# Dot.net
KiCad netlist of a schematic drawn in EAGLE
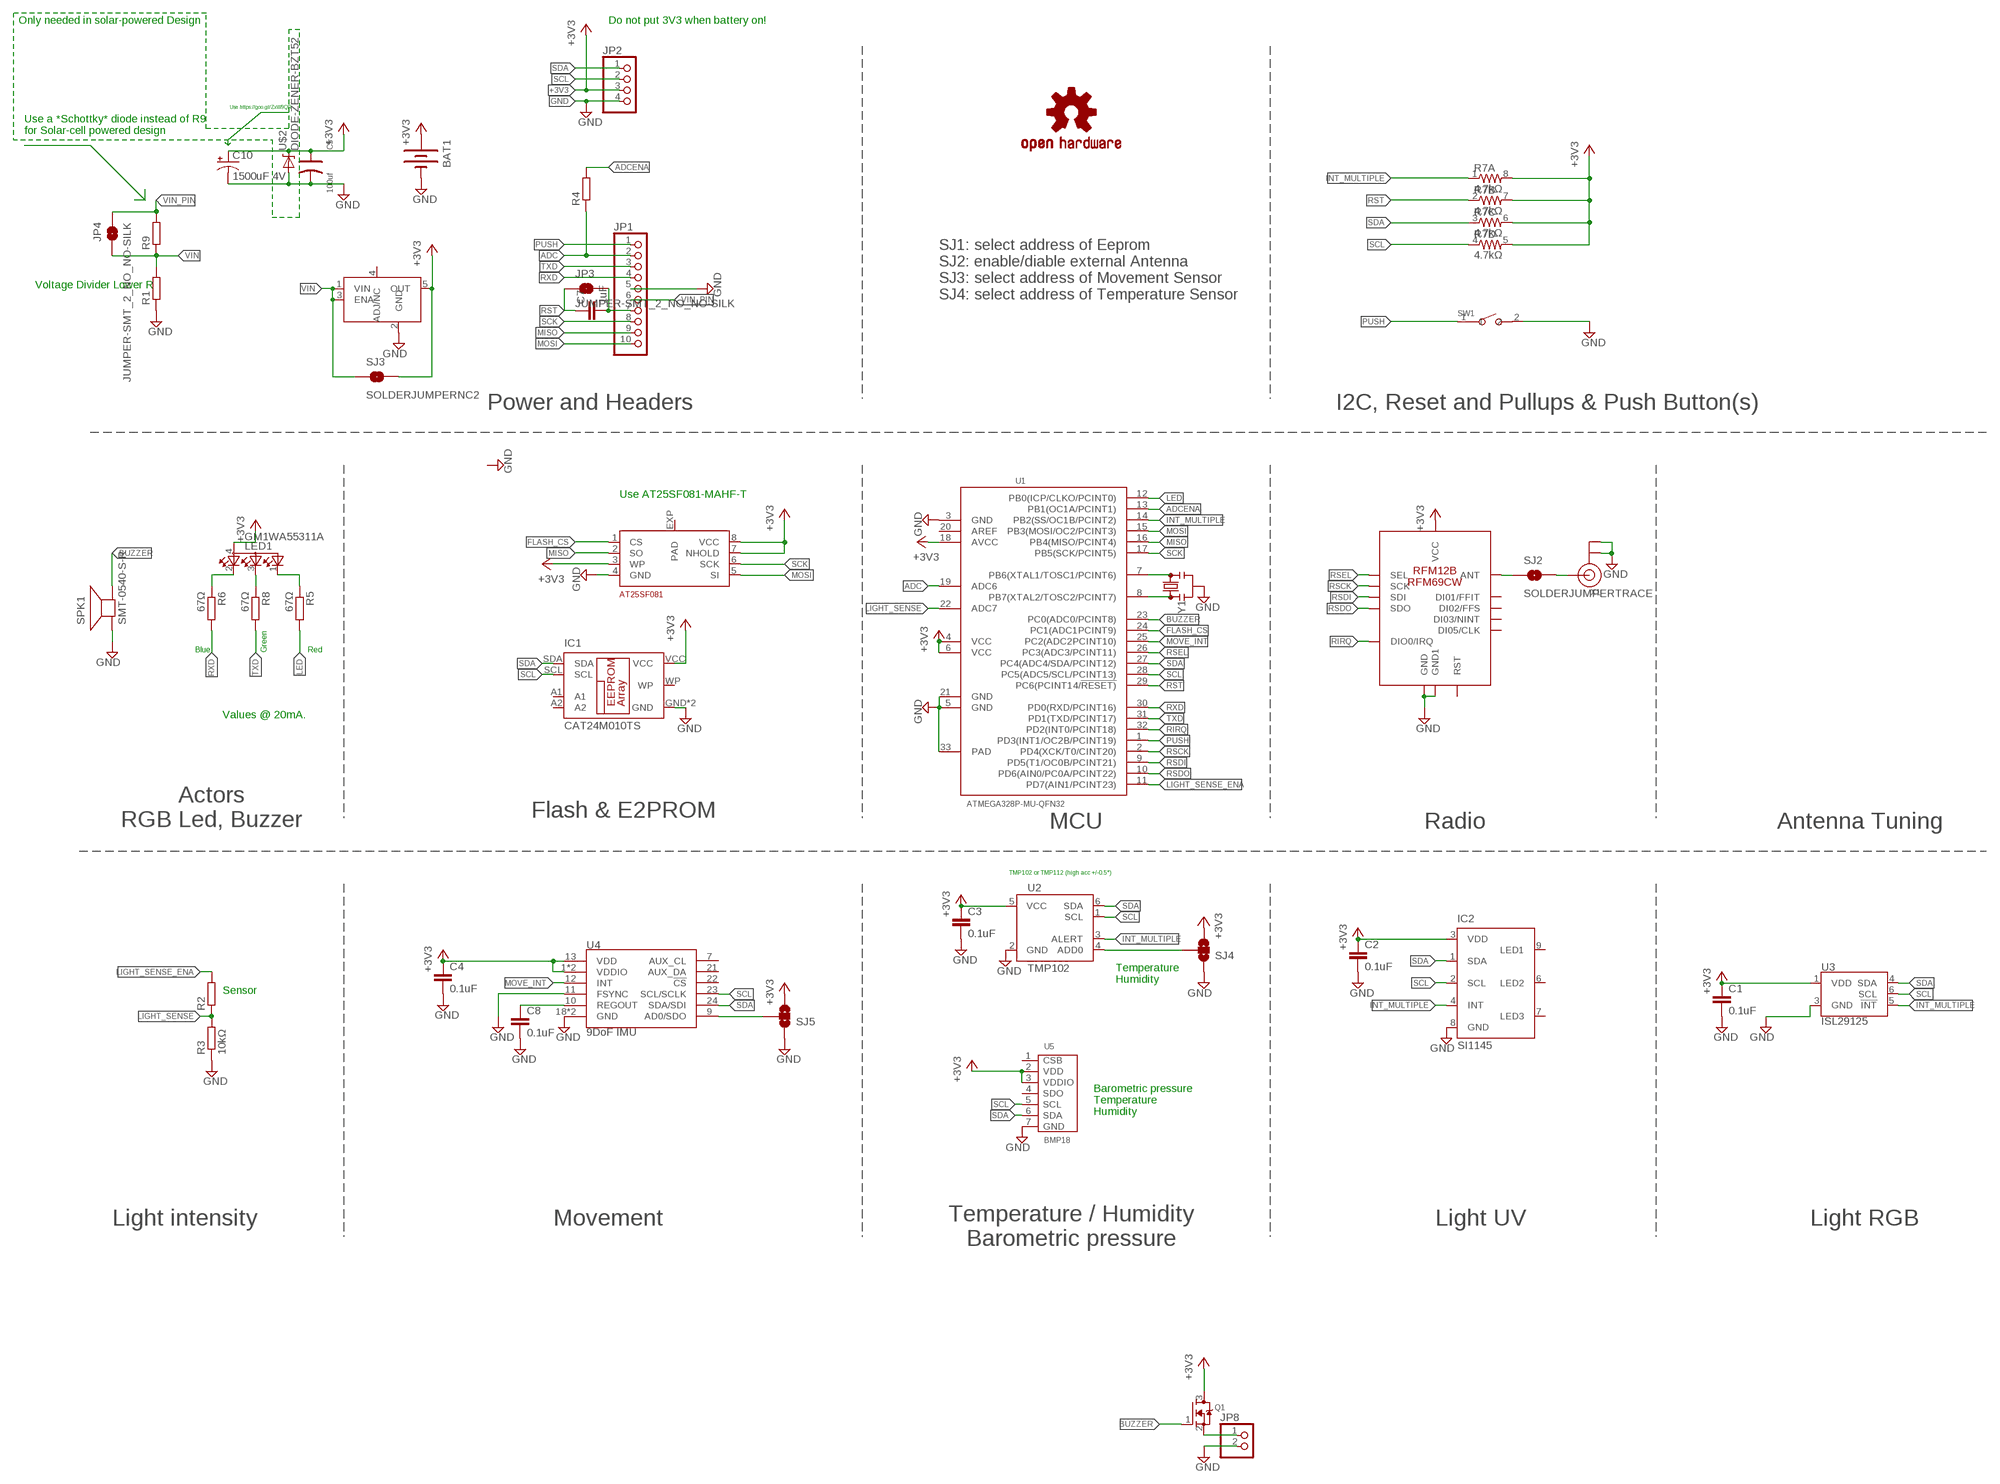
[diagram p0: schematic, sheet 1]
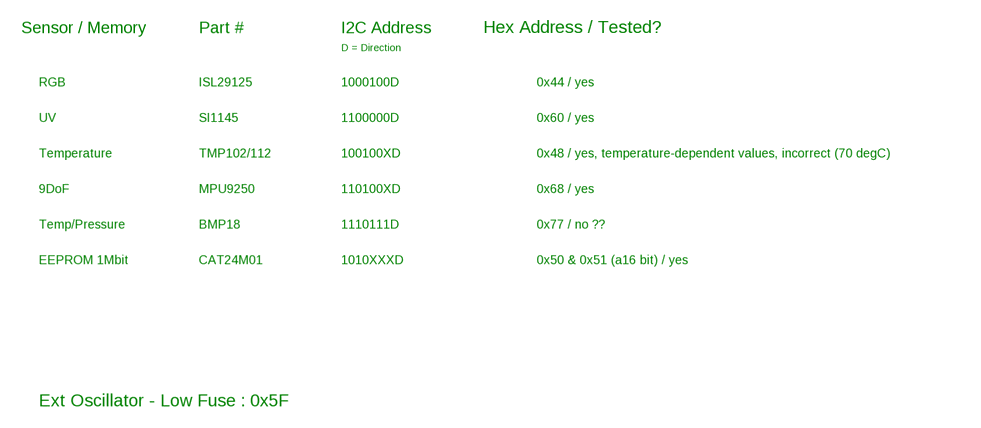
[diagram p1: schematic, sheet 2]

(export (version "E")
  (design (tool "Eeschema 10.0.6"))
  (components
    (comp (ref "BAT1")
      (value "BATTERY20PTH")
      (footprint "eagle-import:BATTCOM_20MM_PTH")
      (libsource (lib "eagle-import") (part "BATTERY20PTH"))
    )
    (comp (ref "C1")
      (value "0.1uF")
      (footprint "eagle-import:C0603")
      (libsource (lib "eagle-import") (part "C-EUC0603"))
    )
    (comp (ref "C2")
      (value "0.1uF")
      (footprint "eagle-import:C0603")
      (libsource (lib "eagle-import") (part "C-EUC0603"))
    )
    (comp (ref "C3")
      (value "0.1uF")
      (footprint "eagle-import:C0603")
      (libsource (lib "eagle-import") (part "C-EUC0603"))
    )
    (comp (ref "C4")
      (value "0.1uF")
      (footprint "eagle-import:C0603")
      (libsource (lib "eagle-import") (part "C-EUC0603"))
    )
    (comp (ref "C5")
      (value "100uf")
      (footprint "eagle-import:AVX-A")
      (fields (field (name "MPN") "TLJA107M006R0800"))
      (libsource (lib "eagle-import") (part "TANTALUM-SMD-100UF-6.3V(AVX-A)"))
    )
    (comp (ref "C7")
      (value "1uF")
      (footprint "eagle-import:C0603")
      (libsource (lib "eagle-import") (part "C-EUC0603"))
    )
    (comp (ref "C8")
      (value "0.1uF")
      (footprint "eagle-import:C0603")
      (libsource (lib "eagle-import") (part "C-EUC0603"))
    )
    (comp (ref "C10")
      (value "1500uF 4V")
      (footprint "eagle-import:CT7343")
      (libsource (lib "eagle-import") (part "CPOL-USCT7343"))
    )
    (comp (ref "IC1")
      (value "CAT24M010TS")
      (footprint "eagle-import:TSSOP8")
      (fields (field (name "MF") "On Semiconductor") (field (name "MPN") "24C00T-E/ST"))
      (libsource (lib "eagle-import") (part "CAT24M01TS0"))
    )
    (comp (ref "IC2")
      (value "SI1145")
      (footprint "eagle-import:QFN-10")
      (libsource (lib "eagle-import") (part "SI1145"))
    )
    (comp (ref "JP1")
      (value "PINHD-1X10")
      (footprint "eagle-import:1X10")
      (libsource (lib "eagle-import") (part "PINHD-1X10"))
    )
    (comp (ref "JP2")
      (value "PINHD-1X4")
      (footprint "eagle-import:1X04")
      (libsource (lib "eagle-import") (part "PINHD-1X4"))
    )
    (comp (ref "JP3")
      (value "JUMPER-SMT_2_NO_NO-SILK")
      (footprint "eagle-import:SMT-JUMPER_2_NO_NO-SILK")
      (libsource (lib "eagle-import") (part "JUMPER-SMT_2_NO_NO-SILK"))
    )
    (comp (ref "JP4")
      (value "JUMPER-SMT_2_NO_NO-SILK")
      (footprint "eagle-import:SMT-JUMPER_2_NO_NO-SILK")
      (libsource (lib "eagle-import") (part "JUMPER-SMT_2_NO_NO-SILK"))
    )
    (comp (ref "JP8")
      (value "PINHD-1X2")
      (footprint "eagle-import:1X02")
      (libsource (lib "eagle-import") (part "PINHD-1X2"))
    )
    (comp (ref "LED1")
      (value "GM1WA55311A")
      (footprint "eagle-import:GM1WA55311A")
      (libsource (lib "eagle-import") (part "GM1WA55311A"))
    )
    (comp (ref "LOGO1")
      (value "OSHW-LOGOS")
      (footprint "eagle-import:OSHW-LOGO-S")
      (libsource (lib "eagle-import") (part "OSHW-LOGOS"))
    )
    (comp (ref "Q1")
      (value "MOSFET-NREFLOW")
      (footprint "eagle-import:SOT23")
      (libsource (lib "eagle-import") (part "MOSFET-NREFLOW"))
    )
    (comp (ref "R1")
      (value "R-EU_R0603")
      (footprint "eagle-import:R0603")
      (libsource (lib "eagle-import") (part "R-EU_R0603"))
    )
    (comp (ref "R2")
      (value "R-EU_R0805")
      (footprint "eagle-import:R0805")
      (libsource (lib "eagle-import") (part "R-EU_R0805"))
    )
    (comp (ref "R3")
      (value "10kΩ")
      (footprint "eagle-import:R0603")
      (libsource (lib "eagle-import") (part "R-EU_R0603"))
    )
    (comp (ref "R4")
      (value "R-EU_R0603")
      (footprint "eagle-import:R0603")
      (libsource (lib "eagle-import") (part "R-EU_R0603"))
    )
    (comp (ref "R5")
      (value "67Ω")
      (footprint "eagle-import:R0603")
      (libsource (lib "eagle-import") (part "R-EU_R0603"))
    )
    (comp (ref "R6")
      (value "67Ω")
      (footprint "eagle-import:R0603")
      (libsource (lib "eagle-import") (part "R-EU_R0603"))
    )
    (comp (ref "R7")
      (value "4.7kΩ")
      (footprint "eagle-import:0603-ARV")
      (libsource (lib "eagle-import") (part "RESISTOR-ARRAY0603-ARV"))
    )
    (comp (ref "R8")
      (value "67Ω")
      (footprint "eagle-import:R0603")
      (libsource (lib "eagle-import") (part "R-EU_R0603"))
    )
    (comp (ref "R9")
      (value "R-EU_R0603")
      (footprint "eagle-import:R0603")
      (libsource (lib "eagle-import") (part "R-EU_R0603"))
    )
    (comp (ref "SJ2")
      (value "SOLDERJUMPERTRACE")
      (footprint "eagle-import:SJ_2S-TRACE")
      (libsource (lib "eagle-import") (part "SOLDERJUMPERTRACE"))
    )
    (comp (ref "SJ3")
      (value "SOLDERJUMPERNC2")
      (footprint "eagle-import:SJ_2S-NOTRACE")
      (libsource (lib "eagle-import") (part "SOLDERJUMPERNC2"))
    )
    (comp (ref "SJ4")
      (value "SOLDERJUMPER_2WAYS")
      (footprint "eagle-import:SJ_3")
      (libsource (lib "eagle-import") (part "SOLDERJUMPER_2WAYS"))
    )
    (comp (ref "SJ5")
      (value "SOLDERJUMPER_2WAYS")
      (footprint "eagle-import:SJ_3")
      (libsource (lib "eagle-import") (part "SOLDERJUMPER_2WAYS"))
    )
    (comp (ref "SPK1")
      (value "SMT-0540-S-R")
      (footprint "eagle-import:SMT-0540-S-R")
      (libsource (lib "eagle-import") (part "SMT-0540-S-R"))
    )
    (comp (ref "SW1")
      (value "SMD-BUTTON(2P-6.0X3.0X2.5MM)-DHT-1163S")
      (footprint "eagle-import:SW2-4.0-6.0X3.0X2.5MM")
      (libsource (lib "eagle-import") (part "SMD-BUTTON(2P-6.0X3.0X2.5MM)-DHT-1163S"))
    )
    (comp (ref "U$1")
      (value "RFM12B/69CW")
      (footprint "eagle-import:RFM12B_69CW")
      (libsource (lib "eagle-import") (part "RFM12B/69CW"))
    )
    (comp (ref "U$2")
      (value "DIODE-ZENER-BZT52")
      (footprint "eagle-import:SOD-323")
      (libsource (lib "eagle-import") (part "DIODE-ZENER-BZT52"))
    )
    (comp (ref "U$3")
      (value "AT25SF081")
      (footprint "eagle-import:DFN-2X3")
      (libsource (lib "eagle-import") (part "AT25SF081"))
    )
    (comp (ref "U$4")
      (value "LDCL015")
      (footprint "eagle-import:SOT23-5")
      (libsource (lib "eagle-import") (part "LDCL015"))
    )
    (comp (ref "U1")
      (value "ATMEGA328P-MU-QFN32")
      (footprint "eagle-import:QFN32G-0.5-5X5MM")
      (fields (field (name "MPN") "ATMEGA328P-MU"))
      (libsource (lib "eagle-import") (part "MCU-ATMEGA328P-MU(QFN32)"))
    )
    (comp (ref "U2")
      (value "TMP102")
      (footprint "eagle-import:SOT563")
      (libsource (lib "eagle-import") (part "TMP102"))
    )
    (comp (ref "U3")
      (value "ISL29125")
      (footprint "eagle-import:ODFN-6")
      (libsource (lib "eagle-import") (part "ISL29125"))
    )
    (comp (ref "U4")
      (value "9DoF IMU")
      (footprint "eagle-import:QFN24-3X3")
      (libsource (lib "eagle-import") (part "MPU-9250"))
    )
    (comp (ref "U5")
      (value "BMP18")
      (footprint "eagle-import:LGA7-1.5-3.8X3.6MM")
      (libsource (lib "eagle-import") (part "PRESSURE-BMP180(LGA7)"))
    )
    (comp (ref "X1")
      (value "ANTENNA_U.FL")
      (footprint "eagle-import:U.FL")
      (libsource (lib "eagle-import") (part "ANTENNA_U.FL"))
    )
    (comp (ref "Y1")
      (value "RESONATORSMD-3.2X1.3")
      (footprint "eagle-import:RESONATOR-SMD-3.2X1.3")
      (libsource (lib "eagle-import") (part "RESONATORSMD-3.2X1.3"))
    )
  )
  (nets
    (net (code "1") (name "+3V3") (class "Default")
      (node (ref "BAT1") (pin "1") (pinfunction "+_1") (pintype "power_in"))
      (node (ref "C1") (pin "1") (pinfunction "1_1") (pintype "passive"))
      (node (ref "C10") (pin "+") (pinfunction "+_+") (pintype "passive"))
      (node (ref "C2") (pin "1") (pinfunction "1_1") (pintype "passive"))
      (node (ref "C3") (pin "1") (pinfunction "1_1") (pintype "passive"))
      (node (ref "C4") (pin "1") (pinfunction "1_1") (pintype "passive"))
      (node (ref "C5") (pin "+") (pinfunction "+_+") (pintype "passive"))
      (node (ref "IC1") (pin "VCC") (pinfunction "VCC_VCC") (pintype "power_in"))
      (node (ref "IC2") (pin "3") (pinfunction "VDD_3") (pintype "power_in"))
      (node (ref "JP2") (pin "3") (pinfunction "3_3") (pintype "passive"))
      (node (ref "LED1") (pin "4") (pinfunction "A_4") (pintype "passive"))
      (node (ref "Q1") (pin "3") (pinfunction "D_3") (pintype "bidirectional"))
      (node (ref "R7") (pin "5") (pinfunction "2_5") (pintype "passive"))
      (node (ref "R7") (pin "6") (pinfunction "2_6") (pintype "passive"))
      (node (ref "R7") (pin "7") (pinfunction "2_7") (pintype "passive"))
      (node (ref "R7") (pin "8") (pinfunction "2_8") (pintype "passive"))
      (node (ref "SJ3") (pin "2") (pinfunction "2_2") (pintype "passive"))
      (node (ref "SJ4") (pin "3") (pinfunction "3_3") (pintype "passive"))
      (node (ref "SJ5") (pin "3") (pinfunction "3_3") (pintype "passive"))
      (node (ref "U$1") (pin "VDD") (pinfunction "VCC_VDD") (pintype "power_in"))
      (node (ref "U$2") (pin "1") (pinfunction "C_1") (pintype "passive"))
      (node (ref "U$3") (pin "3") (pinfunction "WP_3") (pintype "bidirectional"))
      (node (ref "U$3") (pin "7") (pinfunction "NHOLD_7") (pintype "bidirectional"))
      (node (ref "U$3") (pin "8") (pinfunction "VCC_8") (pintype "bidirectional"))
      (node (ref "U$4") (pin "5") (pinfunction "OUT_5") (pintype "bidirectional"))
      (node (ref "U1") (pin "18") (pinfunction "AVCC_18") (pintype "bidirectional"))
      (node (ref "U1") (pin "4") (pinfunction "VCC_4") (pintype "bidirectional"))
      (node (ref "U1") (pin "6") (pinfunction "VCC_6") (pintype "bidirectional"))
      (node (ref "U2") (pin "5") (pinfunction "VCC_5") (pintype "bidirectional"))
      (node (ref "U3") (pin "1") (pinfunction "VDD_1") (pintype "bidirectional"))
      (node (ref "U4") (pin "1") (pinfunction "VDDIO_1") (pintype "bidirectional"))
      (node (ref "U4") (pin "13") (pinfunction "VDD_13") (pintype "bidirectional"))
      (node (ref "U4") (pin "8") (pinfunction "VDDIO_8") (pintype "bidirectional"))
      (node (ref "U5") (pin "2") (pinfunction "VDD_2") (pintype "bidirectional"))
      (node (ref "U5") (pin "3") (pinfunction "VDDIO_3") (pintype "bidirectional"))
    )
    (net (code "2") (name "ADC") (class "Default")
      (node (ref "JP1") (pin "2") (pinfunction "2_2") (pintype "passive"))
      (node (ref "R4") (pin "1") (pinfunction "1_1") (pintype "passive"))
      (node (ref "U1") (pin "19") (pinfunction "ADC6_19") (pintype "bidirectional"))
    )
    (net (code "3") (name "ADCENA") (class "Default")
      (node (ref "R4") (pin "2") (pinfunction "2_2") (pintype "passive"))
      (node (ref "U1") (pin "13") (pinfunction "PB1(OC1A/PCINT1)_13") (pintype "bidirectional"))
    )
    (net (code "4") (name "BUZZER") (class "Default")
      (node (ref "Q1") (pin "1") (pinfunction "G_1") (pintype "bidirectional"))
      (node (ref "SPK1") (pin "+") (pinfunction "-_+") (pintype "passive"))
      (node (ref "U1") (pin "23") (pinfunction "PC0(ADC0/PCINT8)_23") (pintype "bidirectional"))
    )
    (net (code "5") (name "FLASH_CS") (class "Default")
      (node (ref "U$3") (pin "1") (pinfunction "CS_1") (pintype "bidirectional"))
      (node (ref "U1") (pin "24") (pinfunction "PC1(ADC1PCINT9)_24") (pintype "bidirectional"))
    )
    (net (code "6") (name "GND") (class "Default")
      (node (ref "BAT1") (pin "2") (pinfunction "-_2") (pintype "power_in"))
      (node (ref "C1") (pin "2") (pinfunction "2_2") (pintype "passive"))
      (node (ref "C10") (pin "-") (pinfunction "-_-") (pintype "passive"))
      (node (ref "C2") (pin "2") (pinfunction "2_2") (pintype "passive"))
      (node (ref "C3") (pin "2") (pinfunction "2_2") (pintype "passive"))
      (node (ref "C4") (pin "2") (pinfunction "2_2") (pintype "passive"))
      (node (ref "C5") (pin "-") (pinfunction "-_-") (pintype "passive"))
      (node (ref "C8") (pin "2") (pinfunction "2_2") (pintype "passive"))
      (node (ref "IC1") (pin "GND") (pinfunction "GND_GND") (pintype "power_in"))
      (node (ref "IC1") (pin "NC") (pinfunction "GND_NC") (pintype "power_in"))
      (node (ref "IC2") (pin "8") (pinfunction "GND_8") (pintype "power_in"))
      (node (ref "JP1") (pin "5") (pinfunction "5_5") (pintype "passive"))
      (node (ref "JP2") (pin "4") (pinfunction "4_4") (pintype "passive"))
      (node (ref "JP8") (pin "2") (pinfunction "2_2") (pintype "passive"))
      (node (ref "R1") (pin "1") (pinfunction "1_1") (pintype "passive"))
      (node (ref "R3") (pin "1") (pinfunction "1_1") (pintype "passive"))
      (node (ref "SJ4") (pin "1") (pinfunction "1_1") (pintype "passive"))
      (node (ref "SJ5") (pin "1") (pinfunction "1_1") (pintype "passive"))
      (node (ref "SPK1") (pin "-") (pinfunction "+_-") (pintype "passive"))
      (node (ref "SW1") (pin "2") (pinfunction "2_2") (pintype "bidirectional"))
      (node (ref "U$1") (pin "GND") (pinfunction "GND_GND") (pintype "power_in"))
      (node (ref "U$1") (pin "GND1") (pinfunction "GND1_GND1") (pintype "power_in"))
      (node (ref "U$2") (pin "2") (pinfunction "A_2") (pintype "passive"))
      (node (ref "U$3") (pin "4") (pinfunction "GND_4") (pintype "bidirectional"))
      (node (ref "U$4") (pin "2") (pinfunction "GND_2") (pintype "bidirectional"))
      (node (ref "U1") (pin "21") (pinfunction "GND_21") (pintype "bidirectional"))
      (node (ref "U1") (pin "3") (pinfunction "GND_3") (pintype "bidirectional"))
      (node (ref "U1") (pin "33") (pinfunction "PAD_33") (pintype "bidirectional"))
      (node (ref "U1") (pin "5") (pinfunction "GND_5") (pintype "bidirectional"))
      (node (ref "U2") (pin "2") (pinfunction "GND_2") (pintype "bidirectional"))
      (node (ref "U3") (pin "3") (pinfunction "GND_3") (pintype "bidirectional"))
      (node (ref "U4") (pin "11") (pinfunction "FSYNC_11") (pintype "bidirectional"))
      (node (ref "U4") (pin "18") (pinfunction "GND_18") (pintype "bidirectional"))
      (node (ref "U4") (pin "20") (pinfunction "GND_20") (pintype "bidirectional"))
      (node (ref "U5") (pin "7") (pinfunction "GND_7") (pintype "bidirectional"))
      (node (ref "X1") (pin "1") (pinfunction "GND_1") (pintype "passive"))
      (node (ref "X1") (pin "2") (pinfunction "GND_2") (pintype "passive"))
      (node (ref "Y1") (pin "2") (pinfunction "2_2") (pintype "passive"))
    )
    (net (code "7") (name "INT_MULTIPLE") (class "Default")
      (node (ref "IC2") (pin "4") (pinfunction "INT_4") (pintype "open_collector"))
      (node (ref "R7") (pin "1") (pinfunction "1_1") (pintype "passive"))
      (node (ref "U1") (pin "14") (pinfunction "PB2(SS/OC1B/PCINT2)_14") (pintype "bidirectional"))
      (node (ref "U2") (pin "3") (pinfunction "ALERT_3") (pintype "bidirectional"))
      (node (ref "U3") (pin "5") (pinfunction "~{INT}_5") (pintype "bidirectional"))
    )
    (net (code "8") (name "LED") (class "Default")
      (node (ref "R5") (pin "2") (pinfunction "2_2") (pintype "passive"))
      (node (ref "U1") (pin "12") (pinfunction "PB0(ICP/CLKO/PCINT0)_12") (pintype "bidirectional"))
    )
    (net (code "9") (name "LIGHT_SENSE") (class "Default")
      (node (ref "R2") (pin "1") (pinfunction "1_1") (pintype "passive"))
      (node (ref "R3") (pin "2") (pinfunction "2_2") (pintype "passive"))
      (node (ref "U1") (pin "22") (pinfunction "ADC7_22") (pintype "bidirectional"))
    )
    (net (code "10") (name "LIGHT_SENSE_ENA") (class "Default")
      (node (ref "R2") (pin "2") (pinfunction "2_2") (pintype "passive"))
      (node (ref "U1") (pin "11") (pinfunction "PD7(AIN1/PCINT23)_11") (pintype "bidirectional"))
    )
    (net (code "11") (name "MISO") (class "Default")
      (node (ref "JP1") (pin "9") (pinfunction "9_9") (pintype "passive"))
      (node (ref "U$3") (pin "2") (pinfunction "SO_2") (pintype "bidirectional"))
      (node (ref "U1") (pin "16") (pinfunction "PB4(MISO/PCINT4)_16") (pintype "bidirectional"))
    )
    (net (code "12") (name "MOSI") (class "Default")
      (node (ref "JP1") (pin "10") (pinfunction "10_10") (pintype "passive"))
      (node (ref "U$3") (pin "5") (pinfunction "SI_5") (pintype "bidirectional"))
      (node (ref "U1") (pin "15") (pinfunction "PB3(MOSI/OC2/PCINT3)_15") (pintype "bidirectional"))
    )
    (net (code "13") (name "MOVE_INT") (class "Default")
      (node (ref "U1") (pin "25") (pinfunction "PC2(ADC2PCINT10)_25") (pintype "bidirectional"))
      (node (ref "U4") (pin "12") (pinfunction "INT_12") (pintype "bidirectional"))
    )
    (net (code "14") (name "Net-(C7-Pad2)") (class "Default")
      (node (ref "C7") (pin "2") (pinfunction "2_2") (pintype "passive"))
      (node (ref "JP1") (pin "7") (pinfunction "7_7") (pintype "passive"))
      (node (ref "JP3") (pin "2") (pinfunction "2_2") (pintype "passive"))
    )
    (net (code "15") (name "Net-(LED1-CBLUE)") (class "Default")
      (node (ref "LED1") (pin "3") (pinfunction "CBLUE_3") (pintype "passive"))
      (node (ref "R8") (pin "1") (pinfunction "1_1") (pintype "passive"))
    )
    (net (code "16") (name "Net-(LED1-CGREEN)") (class "Default")
      (node (ref "LED1") (pin "1") (pinfunction "CGREEN_1") (pintype "passive"))
      (node (ref "R5") (pin "1") (pinfunction "1_1") (pintype "passive"))
    )
    (net (code "17") (name "Net-(LED1-CRED)") (class "Default")
      (node (ref "LED1") (pin "2") (pinfunction "CRED_2") (pintype "passive"))
      (node (ref "R6") (pin "1") (pinfunction "1_1") (pintype "passive"))
    )
    (net (code "18") (name "Net-(Q1-S)") (class "Default")
      (node (ref "JP8") (pin "1") (pinfunction "1_1") (pintype "passive"))
      (node (ref "Q1") (pin "2") (pinfunction "S_2") (pintype "bidirectional"))
    )
    (net (code "19") (name "Net-(SJ2-Pad1)") (class "Default")
      (node (ref "SJ2") (pin "1") (pinfunction "1_1") (pintype "passive"))
      (node (ref "U$1") (pin "ANT") (pinfunction "ANT_ANT") (pintype "passive"))
    )
    (net (code "20") (name "Net-(U1-PB6(XTAL1{slash}TOSC1{slash}PCINT6))") (class "Default")
      (node (ref "U1") (pin "7") (pinfunction "PB6(XTAL1/TOSC1/PCINT6)_7") (pintype "bidirectional"))
      (node (ref "Y1") (pin "3") (pinfunction "3_3") (pintype "passive"))
    )
    (net (code "21") (name "Net-(U1-PB7(XTAL2{slash}TOSC2{slash}PCINT7))") (class "Default")
      (node (ref "U1") (pin "8") (pinfunction "PB7(XTAL2/TOSC2/PCINT7)_8") (pintype "bidirectional"))
      (node (ref "Y1") (pin "1") (pinfunction "1_1") (pintype "passive"))
    )
    (net (code "22") (name "Net-(U2-ADD0)") (class "Default")
      (node (ref "SJ4") (pin "2") (pinfunction "2_2") (pintype "passive"))
      (node (ref "U2") (pin "4") (pinfunction "ADD0_4") (pintype "bidirectional"))
    )
    (net (code "23") (name "Net-(U4-AD0{slash}SDO)") (class "Default")
      (node (ref "SJ5") (pin "2") (pinfunction "2_2") (pintype "passive"))
      (node (ref "U4") (pin "9") (pinfunction "AD0/SDO_9") (pintype "bidirectional"))
    )
    (net (code "24") (name "Net-(U4-REGOUT)") (class "Default")
      (node (ref "C8") (pin "1") (pinfunction "1_1") (pintype "passive"))
      (node (ref "U4") (pin "10") (pinfunction "REGOUT_10") (pintype "bidirectional"))
    )
    (net (code "25") (name "Net-(X1-SIGNAL)") (class "Default")
      (node (ref "SJ2") (pin "2") (pinfunction "2_2") (pintype "passive"))
      (node (ref "X1") (pin "3") (pinfunction "SIGNAL_3") (pintype "passive"))
    )
    (net (code "26") (name "PUSH") (class "Default")
      (node (ref "JP1") (pin "1") (pinfunction "1_1") (pintype "passive"))
      (node (ref "SW1") (pin "1") (pinfunction "1_1") (pintype "bidirectional"))
      (node (ref "U1") (pin "1") (pinfunction "PD3(INT1/OC2B/PCINT19)_1") (pintype "bidirectional"))
    )
    (net (code "27") (name "RIRQ") (class "Default")
      (node (ref "U$1") (pin "IRQ") (pinfunction "DIO0/IRQ_IRQ") (pintype "open_collector"))
      (node (ref "U1") (pin "32") (pinfunction "PD2(INT0/PCINT18)_32") (pintype "bidirectional"))
    )
    (net (code "28") (name "RSCK") (class "Default")
      (node (ref "U$1") (pin "SCK") (pinfunction "SCK_SCK") (pintype "input"))
      (node (ref "U1") (pin "2") (pinfunction "PD4(XCK/T0/CINT20)_2") (pintype "bidirectional"))
    )
    (net (code "29") (name "RSDI") (class "Default")
      (node (ref "U$1") (pin "SDI") (pinfunction "SDI_SDI") (pintype "input"))
      (node (ref "U1") (pin "9") (pinfunction "PD5(T1/OC0B/PCINT21)_9") (pintype "bidirectional"))
    )
    (net (code "30") (name "RSDO") (class "Default")
      (node (ref "U$1") (pin "SDO") (pinfunction "SDO_SDO") (pintype "output"))
      (node (ref "U1") (pin "10") (pinfunction "PD6(AIN0/PC0A/PCINT22)_10") (pintype "bidirectional"))
    )
    (net (code "31") (name "RSEL") (class "Default")
      (node (ref "U$1") (pin "SEL") (pinfunction "SEL_SEL") (pintype "input"))
      (node (ref "U1") (pin "26") (pinfunction "PC3(ADC3/PCINT11)_26") (pintype "bidirectional"))
    )
    (net (code "32") (name "RST") (class "Default")
      (node (ref "C7") (pin "1") (pinfunction "1_1") (pintype "passive"))
      (node (ref "JP3") (pin "1") (pinfunction "1_1") (pintype "passive"))
      (node (ref "R7") (pin "2") (pinfunction "1_2") (pintype "passive"))
      (node (ref "U1") (pin "29") (pinfunction "PC6(PCINT14/~{RESET})_29") (pintype "bidirectional"))
    )
    (net (code "33") (name "RXD") (class "Default")
      (node (ref "JP1") (pin "4") (pinfunction "4_4") (pintype "passive"))
      (node (ref "R6") (pin "2") (pinfunction "2_2") (pintype "passive"))
      (node (ref "U1") (pin "30") (pinfunction "PD0(RXD/PCINT16)_30") (pintype "bidirectional"))
    )
    (net (code "34") (name "SCK") (class "Default")
      (node (ref "JP1") (pin "8") (pinfunction "8_8") (pintype "passive"))
      (node (ref "U$3") (pin "6") (pinfunction "SCK_6") (pintype "bidirectional"))
      (node (ref "U1") (pin "17") (pinfunction "PB5(SCK/PCINT5)_17") (pintype "bidirectional"))
    )
    (net (code "35") (name "SCL") (class "Default")
      (node (ref "IC1") (pin "SCL") (pinfunction "SCL_SCL") (pintype "input"))
      (node (ref "IC2") (pin "2") (pinfunction "SCL_2") (pintype "input"))
      (node (ref "JP2") (pin "2") (pinfunction "2_2") (pintype "passive"))
      (node (ref "R7") (pin "4") (pinfunction "1_4") (pintype "passive"))
      (node (ref "U1") (pin "28") (pinfunction "PC5(ADC5/SCL/PCINT13)_28") (pintype "bidirectional"))
      (node (ref "U2") (pin "1") (pinfunction "SCL_1") (pintype "bidirectional"))
      (node (ref "U3") (pin "6") (pinfunction "SCL_6") (pintype "bidirectional"))
      (node (ref "U4") (pin "23") (pinfunction "SCL/SCLK_23") (pintype "bidirectional"))
      (node (ref "U5") (pin "5") (pinfunction "SCL_5") (pintype "bidirectional"))
    )
    (net (code "36") (name "SDA") (class "Default")
      (node (ref "IC1") (pin "SDA") (pinfunction "SDA_SDA") (pintype "bidirectional"))
      (node (ref "IC2") (pin "1") (pinfunction "SDA_1") (pintype "bidirectional"))
      (node (ref "JP2") (pin "1") (pinfunction "1_1") (pintype "passive"))
      (node (ref "R7") (pin "3") (pinfunction "1_3") (pintype "passive"))
      (node (ref "U1") (pin "27") (pinfunction "PC4(ADC4/SDA/PCINT12)_27") (pintype "bidirectional"))
      (node (ref "U2") (pin "6") (pinfunction "SDA_6") (pintype "bidirectional"))
      (node (ref "U3") (pin "4") (pinfunction "SDA_4") (pintype "bidirectional"))
      (node (ref "U4") (pin "24") (pinfunction "SDA/SDI_24") (pintype "bidirectional"))
      (node (ref "U5") (pin "6") (pinfunction "SDA_6") (pintype "bidirectional"))
    )
    (net (code "37") (name "TXD") (class "Default")
      (node (ref "JP1") (pin "3") (pinfunction "3_3") (pintype "passive"))
      (node (ref "R8") (pin "2") (pinfunction "2_2") (pintype "passive"))
      (node (ref "U1") (pin "31") (pinfunction "PD1(TXD/PCINT17)_31") (pintype "bidirectional"))
    )
    (net (code "38") (name "VIN") (class "Default")
      (node (ref "JP4") (pin "2") (pinfunction "2_2") (pintype "passive"))
      (node (ref "R1") (pin "2") (pinfunction "2_2") (pintype "passive"))
      (node (ref "R9") (pin "1") (pinfunction "1_1") (pintype "passive"))
      (node (ref "SJ3") (pin "1") (pinfunction "1_1") (pintype "passive"))
      (node (ref "U$4") (pin "1") (pinfunction "VIN_1") (pintype "bidirectional"))
      (node (ref "U$4") (pin "3") (pinfunction "ENA_3") (pintype "bidirectional"))
    )
    (net (code "39") (name "VIN_PIN") (class "Default")
      (node (ref "JP1") (pin "6") (pinfunction "6_6") (pintype "passive"))
      (node (ref "JP4") (pin "1") (pinfunction "1_1") (pintype "passive"))
      (node (ref "R9") (pin "2") (pinfunction "2_2") (pintype "passive"))
    )
    (net (code "40") (name "unconnected-(IC1-PadA1)") (class "Default")
      (node (ref "IC1") (pin "A1") (pinfunction "A1_A1") (pintype "bidirectional"))
    )
    (net (code "41") (name "unconnected-(IC1-PadA2)") (class "Default")
      (node (ref "IC1") (pin "A2") (pinfunction "A2_A2") (pintype "bidirectional"))
    )
    (net (code "42") (name "unconnected-(IC1-PadWP)") (class "Default")
      (node (ref "IC1") (pin "WP") (pinfunction "WP_WP") (pintype "bidirectional"))
    )
    (net (code "43") (name "unconnected-(IC2-LED1-Pad9)") (class "Default")
      (node (ref "IC2") (pin "9") (pinfunction "LED1_9") (pintype "output"))
    )
    (net (code "44") (name "unconnected-(IC2-LED2-Pad6)") (class "Default")
      (node (ref "IC2") (pin "6") (pinfunction "LED2_6") (pintype "output"))
    )
    (net (code "45") (name "unconnected-(IC2-LED3-Pad7)") (class "Default")
      (node (ref "IC2") (pin "7") (pinfunction "LED3_7") (pintype "output"))
    )
    (net (code "46") (name "unconnected-(U$1-DI01{slash}FFIT-PadFFIT)") (class "Default")
      (node (ref "U$1") (pin "FFIT") (pinfunction "DI01/FFIT_FFIT") (pintype "passive"))
    )
    (net (code "47") (name "unconnected-(U$1-DI02{slash}FFS-PadFFS)") (class "Default")
      (node (ref "U$1") (pin "FFS") (pinfunction "DI02/FFS_FFS") (pintype "bidirectional"))
    )
    (net (code "48") (name "unconnected-(U$1-DI03{slash}NINT-PadNINT)") (class "Default")
      (node (ref "U$1") (pin "NINT") (pinfunction "DI03/NINT_NINT") (pintype "passive"))
    )
    (net (code "49") (name "unconnected-(U$1-DI05{slash}CLK-PadCLK)") (class "Default")
      (node (ref "U$1") (pin "CLK") (pinfunction "DI05/CLK_CLK") (pintype "passive"))
    )
    (net (code "50") (name "unconnected-(U$1-PadRST)") (class "Default")
      (node (ref "U$1") (pin "RST") (pinfunction "RST_RST") (pintype "open_collector"))
    )
    (net (code "51") (name "unconnected-(U$3-PAD-PadEXP)") (class "Default")
      (node (ref "U$3") (pin "EXP") (pinfunction "PAD_EXP") (pintype "bidirectional"))
    )
    (net (code "52") (name "unconnected-(U$4-ADJ{slash}NC-Pad4)") (class "Default")
      (node (ref "U$4") (pin "4") (pinfunction "ADJ/NC_4") (pintype "bidirectional"))
    )
    (net (code "53") (name "unconnected-(U1-AREF-Pad20)") (class "Default")
      (node (ref "U1") (pin "20") (pinfunction "AREF_20") (pintype "bidirectional"))
    )
    (net (code "54") (name "unconnected-(U4-AUX_CL-Pad7)") (class "Default")
      (node (ref "U4") (pin "7") (pinfunction "AUX_CL_7") (pintype "bidirectional"))
    )
    (net (code "55") (name "unconnected-(U4-AUX_DA-Pad21)") (class "Default")
      (node (ref "U4") (pin "21") (pinfunction "AUX_DA_21") (pintype "bidirectional"))
    )
    (net (code "56") (name "unconnected-(U4-~{CS}-Pad22)") (class "Default")
      (node (ref "U4") (pin "22") (pinfunction "~{CS}_22") (pintype "bidirectional"))
    )
    (net (code "57") (name "unconnected-(U5-CSB-Pad1)") (class "Default")
      (node (ref "U5") (pin "1") (pinfunction "CSB_1") (pintype "bidirectional"))
    )
    (net (code "58") (name "unconnected-(U5-SDO-Pad4)") (class "Default")
      (node (ref "U5") (pin "4") (pinfunction "SDO_4") (pintype "bidirectional"))
    )
  )
)
